# psiboard.net
KiCad netlist of a schematic drawn in EAGLE
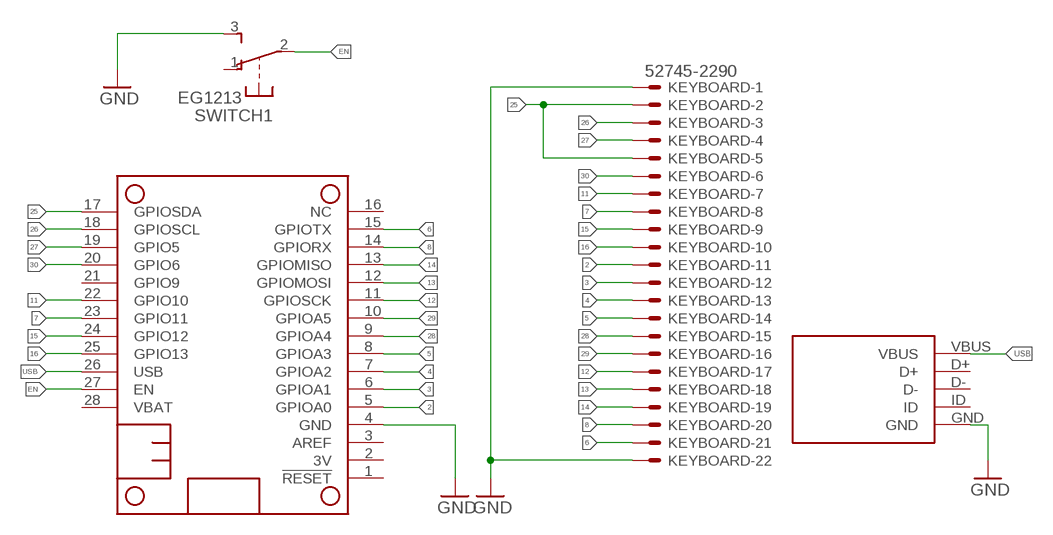
[diagram p0: schematic, sheet 1]

(export (version "E")
  (design (tool "Eeschema 10.0.6"))
  (components
    (comp (ref "FEATHER")
      (value "FEATHERWING_NODIM")
      (footprint "eagle-import:FEATHERWING_DIM")
      (libsource (lib "eagle-import") (part "FEATHERWING_NODIM"))
    )
    (comp (ref "KEYBOARD")
      (value "52745-2290")
      (footprint "eagle-import:52745-2290")
      (fields (field (name "MF") "MOLEX"))
      (libsource (lib "eagle-import") (part "52745-2290"))
    )
    (comp (ref "SWITCH")
      (value "EG1213")
      (footprint "eagle-import:EG1213")
      (libsource (lib "eagle-import") (part "EG1213"))
    )
    (comp (ref "U$2")
      (value "USB_MICRO_PWR")
      (footprint "eagle-import:MICROBUILDER_4UCONN_20329")
      (libsource (lib "eagle-import") (part "USB_MICRO_PWR"))
    )
  )
  (nets
    (net (code "1") (name "/3V") (class "Default")
      (node (ref "FEATHER") (pin "2") (pinfunction "3V_2") (pintype "power_in"))
    )
    (net (code "2") (name "/VBAT") (class "Default")
      (node (ref "FEATHER") (pin "28") (pinfunction "VBAT_28") (pintype "power_in"))
    )
    (net (code "3") (name "2") (class "Default")
      (node (ref "FEATHER") (pin "5") (pinfunction "GPIOA0_5") (pintype "bidirectional"))
      (node (ref "KEYBOARD") (pin "11") (pinfunction "S_11") (pintype "passive"))
    )
    (net (code "4") (name "3") (class "Default")
      (node (ref "FEATHER") (pin "6") (pinfunction "GPIOA1_6") (pintype "bidirectional"))
      (node (ref "KEYBOARD") (pin "12") (pinfunction "S_12") (pintype "passive"))
    )
    (net (code "5") (name "4") (class "Default")
      (node (ref "FEATHER") (pin "7") (pinfunction "GPIOA2_7") (pintype "bidirectional"))
      (node (ref "KEYBOARD") (pin "13") (pinfunction "S_13") (pintype "passive"))
    )
    (net (code "6") (name "5") (class "Default")
      (node (ref "FEATHER") (pin "8") (pinfunction "GPIOA3_8") (pintype "bidirectional"))
      (node (ref "KEYBOARD") (pin "14") (pinfunction "S_14") (pintype "passive"))
    )
    (net (code "7") (name "6") (class "Default")
      (node (ref "FEATHER") (pin "15") (pinfunction "GPIOTX_15") (pintype "bidirectional"))
      (node (ref "KEYBOARD") (pin "21") (pinfunction "S_21") (pintype "passive"))
    )
    (net (code "8") (name "7") (class "Default")
      (node (ref "FEATHER") (pin "23") (pinfunction "GPIO11_23") (pintype "bidirectional"))
      (node (ref "KEYBOARD") (pin "8") (pinfunction "S_8") (pintype "passive"))
    )
    (net (code "9") (name "8") (class "Default")
      (node (ref "FEATHER") (pin "14") (pinfunction "GPIORX_14") (pintype "bidirectional"))
      (node (ref "KEYBOARD") (pin "20") (pinfunction "S_20") (pintype "passive"))
    )
    (net (code "10") (name "11") (class "Default")
      (node (ref "FEATHER") (pin "22") (pinfunction "GPIO10_22") (pintype "bidirectional"))
      (node (ref "KEYBOARD") (pin "7") (pinfunction "S_7") (pintype "passive"))
    )
    (net (code "11") (name "12") (class "Default")
      (node (ref "FEATHER") (pin "11") (pinfunction "GPIOSCK_11") (pintype "bidirectional"))
      (node (ref "KEYBOARD") (pin "17") (pinfunction "S_17") (pintype "passive"))
    )
    (net (code "12") (name "13") (class "Default")
      (node (ref "FEATHER") (pin "12") (pinfunction "GPIOMOSI_12") (pintype "bidirectional"))
      (node (ref "KEYBOARD") (pin "18") (pinfunction "S_18") (pintype "passive"))
    )
    (net (code "13") (name "14") (class "Default")
      (node (ref "FEATHER") (pin "13") (pinfunction "GPIOMISO_13") (pintype "bidirectional"))
      (node (ref "KEYBOARD") (pin "19") (pinfunction "S_19") (pintype "passive"))
    )
    (net (code "14") (name "15") (class "Default")
      (node (ref "FEATHER") (pin "24") (pinfunction "GPIO12_24") (pintype "bidirectional"))
      (node (ref "KEYBOARD") (pin "9") (pinfunction "S_9") (pintype "passive"))
    )
    (net (code "15") (name "16") (class "Default")
      (node (ref "FEATHER") (pin "25") (pinfunction "GPIO13_25") (pintype "bidirectional"))
      (node (ref "KEYBOARD") (pin "10") (pinfunction "S_10") (pintype "passive"))
    )
    (net (code "16") (name "25") (class "Default")
      (node (ref "FEATHER") (pin "17") (pinfunction "GPIOSDA_17") (pintype "bidirectional"))
      (node (ref "KEYBOARD") (pin "2") (pinfunction "S_2") (pintype "passive"))
      (node (ref "KEYBOARD") (pin "5") (pinfunction "S_5") (pintype "passive"))
    )
    (net (code "17") (name "26") (class "Default")
      (node (ref "FEATHER") (pin "18") (pinfunction "GPIOSCL_18") (pintype "bidirectional"))
      (node (ref "KEYBOARD") (pin "3") (pinfunction "S_3") (pintype "passive"))
    )
    (net (code "18") (name "27") (class "Default")
      (node (ref "FEATHER") (pin "19") (pinfunction "GPIO5_19") (pintype "bidirectional"))
      (node (ref "KEYBOARD") (pin "4") (pinfunction "S_4") (pintype "passive"))
    )
    (net (code "19") (name "28") (class "Default")
      (node (ref "FEATHER") (pin "9") (pinfunction "GPIOA4_9") (pintype "bidirectional"))
      (node (ref "KEYBOARD") (pin "15") (pinfunction "S_15") (pintype "passive"))
    )
    (net (code "20") (name "29") (class "Default")
      (node (ref "FEATHER") (pin "10") (pinfunction "GPIOA5_10") (pintype "bidirectional"))
      (node (ref "KEYBOARD") (pin "16") (pinfunction "S_16") (pintype "passive"))
    )
    (net (code "21") (name "30") (class "Default")
      (node (ref "FEATHER") (pin "20") (pinfunction "GPIO6_20") (pintype "bidirectional"))
      (node (ref "KEYBOARD") (pin "6") (pinfunction "S_6") (pintype "passive"))
    )
    (net (code "22") (name "EN") (class "Default")
      (node (ref "FEATHER") (pin "27") (pinfunction "EN_27") (pintype "passive"))
      (node (ref "SWITCH") (pin "2") (pinfunction "P_2") (pintype "passive"))
    )
    (net (code "23") (name "GND") (class "Default")
      (node (ref "FEATHER") (pin "4") (pinfunction "GND_4") (pintype "power_in"))
      (node (ref "KEYBOARD") (pin "1") (pinfunction "S_1") (pintype "passive"))
      (node (ref "KEYBOARD") (pin "22") (pinfunction "S_22") (pintype "passive"))
      (node (ref "SWITCH") (pin "3") (pinfunction "S_3") (pintype "passive"))
      (node (ref "U$2") (pin "GND") (pinfunction "GND_GND") (pintype "bidirectional"))
    )
    (net (code "24") (name "USB") (class "Default")
      (node (ref "FEATHER") (pin "26") (pinfunction "USB_26") (pintype "power_in"))
      (node (ref "U$2") (pin "VBUS") (pinfunction "VBUS_VBUS") (pintype "bidirectional"))
    )
    (net (code "25") (name "unconnected-(FEATHER-AREF-Pad3)") (class "Default")
      (node (ref "FEATHER") (pin "3") (pinfunction "AREF_3") (pintype "passive"))
    )
    (net (code "26") (name "unconnected-(FEATHER-GPIO9-Pad21)") (class "Default")
      (node (ref "FEATHER") (pin "21") (pinfunction "GPIO9_21") (pintype "bidirectional"))
    )
    (net (code "27") (name "unconnected-(FEATHER-NC-Pad16)") (class "Default")
      (node (ref "FEATHER") (pin "16") (pinfunction "NC_16") (pintype "passive"))
    )
    (net (code "28") (name "unconnected-(FEATHER-~{RESET}-Pad1)") (class "Default")
      (node (ref "FEATHER") (pin "1") (pinfunction "~{RESET}_1") (pintype "input"))
    )
    (net (code "29") (name "unconnected-(SWITCHA-O-Pad1)") (class "Default")
      (node (ref "SWITCH") (pin "1") (pinfunction "O_1") (pintype "passive"))
    )
    (net (code "30") (name "unconnected-(U$2-PadD+)") (class "Default")
      (node (ref "U$2") (pin "D+") (pinfunction "D+_D+") (pintype "bidirectional"))
    )
    (net (code "31") (name "unconnected-(U$2-PadD-)") (class "Default")
      (node (ref "U$2") (pin "D-") (pinfunction "D-_D-") (pintype "bidirectional"))
    )
    (net (code "32") (name "unconnected-(U$2-PadID)") (class "Default")
      (node (ref "U$2") (pin "ID") (pinfunction "ID_ID") (pintype "bidirectional"))
    )
  )
)
